# Sheet1.net
KiCad netlist of a schematic drawn in Altium Designer
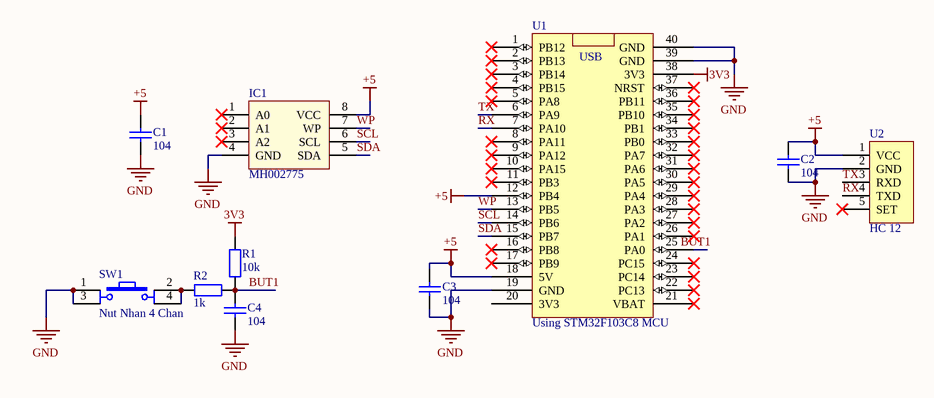
[diagram p0: Sheet1.SchDoc]

(export (version "E")
  (design (tool "Eeschema 10.0.6"))
  (components
    (comp (ref "C1")
      (value "104")
      (footprint "tu 0805")
      (description "Dán")
      (libsource (lib "THU VIEN SCH") (part "Tu 0805 104 50V 10%"))
    )
    (comp (ref "C2")
      (value "104")
      (footprint "tu 0805")
      (description "Dán")
      (libsource (lib "THU VIEN SCH") (part "Tu 0805 104 50V 10%"))
    )
    (comp (ref "C3")
      (value "104")
      (footprint "tu 0805")
      (description "Dán")
      (libsource (lib "THU VIEN SCH") (part "Tu 0805 104 50V 10%"))
    )
    (comp (ref "C4")
      (value "104")
      (footprint "tu 0805")
      (description "Dán")
      (libsource (lib "THU VIEN SCH") (part "Tu 0805 104 50V 10%"))
    )
    (comp (ref "IC1")
      (value "MH002775")
      (footprint "DIP8")
      (description "Dán")
      (libsource (lib "THU VIEN SCH") (part "24Cxx_MH"))
    )
    (comp (ref "R1")
      (value "10k")
      (footprint "tro smd 0805")
      (description "Dán")
      (libsource (lib "THU VIEN SCH") (part "Tro 0805 1% 10k"))
    )
    (comp (ref "R2")
      (value "1k")
      (footprint "tro smd 0805")
      (description "Dán")
      (libsource (lib "THU VIEN SCH") (part "Tro 0805 1% 3.3k"))
    )
    (comp (ref "SW1")
      (value "Nut Nhan 4 Chan")
      (footprint "SW4")
      (description "Cắm")
      (libsource (lib "THU VIEN SCH") (part "Nut Nhan 4 Chan"))
    )
    (comp (ref "U1")
      (value "Using STM32F103C8 MCU")
      (footprint "STM32 BluePill")
      (libsource (lib "My_Lib") (part "BluePill"))
    )
    (comp (ref "U2") (value "HC 12") (footprint "HC 12") (libsource (lib "My_Lib") (part "HC 12")))
  )
  (nets
    (net (code "1") (name "+5") (class "Default")
      (node (ref "C1") (pin "1") (pinfunction "1_1") (pintype "passive"))
      (node (ref "C2") (pin "1") (pinfunction "1_1") (pintype "passive"))
      (node (ref "C3") (pin "1") (pinfunction "1_1") (pintype "passive"))
      (node (ref "IC1") (pin "8") (pinfunction "VCC_8") (pintype "power_in"))
      (node (ref "U1") (pin "12") (pinfunction "PB4_12") (pintype "bidirectional"))
      (node (ref "U1") (pin "18") (pinfunction "5V_18") (pintype "power_in"))
      (node (ref "U2") (pin "1") (pinfunction "VCC_1") (pintype "passive"))
    )
    (net (code "2") (name "/BUT1") (class "Default")
      (node (ref "C4") (pin "1") (pinfunction "1_1") (pintype "passive"))
      (node (ref "R1") (pin "1") (pinfunction "1_1") (pintype "passive"))
      (node (ref "R2") (pin "2") (pinfunction "2_2") (pintype "passive"))
    )
    (net (code "3") (name "/RX") (class "Default")
      (node (ref "U1") (pin "7") (pinfunction "PA10_7") (pintype "bidirectional"))
      (node (ref "U2") (pin "4") (pinfunction "TXD_4") (pintype "passive"))
    )
    (net (code "4") (name "/SCL") (class "Default")
      (node (ref "IC1") (pin "6") (pinfunction "SCL_6") (pintype "passive"))
      (node (ref "U1") (pin "14") (pinfunction "PB6_14") (pintype "bidirectional"))
    )
    (net (code "5") (name "/SDA") (class "Default")
      (node (ref "IC1") (pin "5") (pinfunction "SDA_5") (pintype "passive"))
      (node (ref "U1") (pin "15") (pinfunction "PB7_15") (pintype "bidirectional"))
    )
    (net (code "6") (name "/TX") (class "Default")
      (node (ref "U1") (pin "6") (pinfunction "PA9_6") (pintype "bidirectional"))
      (node (ref "U2") (pin "3") (pinfunction "RXD_3") (pintype "passive"))
    )
    (net (code "7") (name "/WP") (class "Default")
      (node (ref "IC1") (pin "7") (pinfunction "WP_7") (pintype "passive"))
      (node (ref "U1") (pin "13") (pinfunction "PB5_13") (pintype "bidirectional"))
    )
    (net (code "8") (name "3V3") (class "Default")
      (node (ref "R1") (pin "2") (pinfunction "2_2") (pintype "passive"))
      (node (ref "U1") (pin "38") (pinfunction "3V3_38") (pintype "power_in"))
    )
    (net (code "9") (name "GND") (class "Default")
      (node (ref "C1") (pin "2") (pinfunction "2_2") (pintype "passive"))
      (node (ref "C2") (pin "2") (pinfunction "2_2") (pintype "passive"))
      (node (ref "C3") (pin "2") (pinfunction "2_2") (pintype "passive"))
      (node (ref "C4") (pin "2") (pinfunction "2_2") (pintype "passive"))
      (node (ref "IC1") (pin "4") (pinfunction "GND_4") (pintype "power_in"))
      (node (ref "SW1") (pin "1") (pintype "passive"))
      (node (ref "SW1") (pin "3") (pintype "passive"))
      (node (ref "U1") (pin "19") (pinfunction "GND_19") (pintype "power_in"))
      (node (ref "U1") (pin "39") (pinfunction "GND_39") (pintype "power_in"))
      (node (ref "U1") (pin "40") (pinfunction "GND_40") (pintype "power_in"))
      (node (ref "U2") (pin "2") (pinfunction "GND_2") (pintype "passive"))
    )
    (net (code "10") (name "Net-(R2-Pad1)") (class "Default")
      (node (ref "R2") (pin "1") (pinfunction "1_1") (pintype "passive"))
      (node (ref "SW1") (pin "2") (pintype "passive"))
      (node (ref "SW1") (pin "4") (pintype "passive"))
    )
    (net (code "11") (name "unconnected-(IC1-A0-Pad1)") (class "Default")
      (node (ref "IC1") (pin "1") (pinfunction "A0_1") (pintype "passive+no_connect"))
    )
    (net (code "12") (name "unconnected-(IC1-A1-Pad2)") (class "Default")
      (node (ref "IC1") (pin "2") (pinfunction "A1_2") (pintype "passive+no_connect"))
    )
    (net (code "13") (name "unconnected-(IC1-A2-Pad3)") (class "Default")
      (node (ref "IC1") (pin "3") (pinfunction "A2_3") (pintype "passive+no_connect"))
    )
    (net (code "14") (name "unconnected-(U1-3V3-Pad20)") (class "Default")
      (node (ref "U1") (pin "20") (pinfunction "3V3_20") (pintype "power_in"))
    )
    (net (code "15") (name "unconnected-(U1-NRST-Pad37)") (class "Default")
      (node (ref "U1") (pin "37") (pinfunction "NRST_37") (pintype "bidirectional+no_connect"))
    )
    (net (code "16") (name "unconnected-(U1-PA0-Pad25)") (class "Default")
      (node (ref "U1") (pin "25") (pinfunction "PA0_25") (pintype "bidirectional"))
    )
    (net (code "17") (name "unconnected-(U1-PA1-Pad26)") (class "Default")
      (node (ref "U1") (pin "26") (pinfunction "PA1_26") (pintype "bidirectional+no_connect"))
    )
    (net (code "18") (name "unconnected-(U1-PA2-Pad27)") (class "Default")
      (node (ref "U1") (pin "27") (pinfunction "PA2_27") (pintype "bidirectional+no_connect"))
    )
    (net (code "19") (name "unconnected-(U1-PA3-Pad28)") (class "Default")
      (node (ref "U1") (pin "28") (pinfunction "PA3_28") (pintype "bidirectional+no_connect"))
    )
    (net (code "20") (name "unconnected-(U1-PA4-Pad29)") (class "Default")
      (node (ref "U1") (pin "29") (pinfunction "PA4_29") (pintype "bidirectional+no_connect"))
    )
    (net (code "21") (name "unconnected-(U1-PA5-Pad30)") (class "Default")
      (node (ref "U1") (pin "30") (pinfunction "PA5_30") (pintype "bidirectional+no_connect"))
    )
    (net (code "22") (name "unconnected-(U1-PA6-Pad31)") (class "Default")
      (node (ref "U1") (pin "31") (pinfunction "PA6_31") (pintype "bidirectional+no_connect"))
    )
    (net (code "23") (name "unconnected-(U1-PA7-Pad32)") (class "Default")
      (node (ref "U1") (pin "32") (pinfunction "PA7_32") (pintype "bidirectional+no_connect"))
    )
    (net (code "24") (name "unconnected-(U1-PA8-Pad5)") (class "Default")
      (node (ref "U1") (pin "5") (pinfunction "PA8_5") (pintype "bidirectional+no_connect"))
    )
    (net (code "25") (name "unconnected-(U1-PA11-Pad8)") (class "Default")
      (node (ref "U1") (pin "8") (pinfunction "PA11_8") (pintype "bidirectional+no_connect"))
    )
    (net (code "26") (name "unconnected-(U1-PA12-Pad9)") (class "Default")
      (node (ref "U1") (pin "9") (pinfunction "PA12_9") (pintype "bidirectional+no_connect"))
    )
    (net (code "27") (name "unconnected-(U1-PA15-Pad10)") (class "Default")
      (node (ref "U1") (pin "10") (pinfunction "PA15_10") (pintype "bidirectional+no_connect"))
    )
    (net (code "28") (name "unconnected-(U1-PB0-Pad33)") (class "Default")
      (node (ref "U1") (pin "33") (pinfunction "PB0_33") (pintype "bidirectional+no_connect"))
    )
    (net (code "29") (name "unconnected-(U1-PB1-Pad34)") (class "Default")
      (node (ref "U1") (pin "34") (pinfunction "PB1_34") (pintype "bidirectional+no_connect"))
    )
    (net (code "30") (name "unconnected-(U1-PB3-Pad11)") (class "Default")
      (node (ref "U1") (pin "11") (pinfunction "PB3_11") (pintype "bidirectional+no_connect"))
    )
    (net (code "31") (name "unconnected-(U1-PB8-Pad16)") (class "Default")
      (node (ref "U1") (pin "16") (pinfunction "PB8_16") (pintype "bidirectional+no_connect"))
    )
    (net (code "32") (name "unconnected-(U1-PB9-Pad17)") (class "Default")
      (node (ref "U1") (pin "17") (pinfunction "PB9_17") (pintype "bidirectional+no_connect"))
    )
    (net (code "33") (name "unconnected-(U1-PB10-Pad35)") (class "Default")
      (node (ref "U1") (pin "35") (pinfunction "PB10_35") (pintype "bidirectional+no_connect"))
    )
    (net (code "34") (name "unconnected-(U1-PB11-Pad36)") (class "Default")
      (node (ref "U1") (pin "36") (pinfunction "PB11_36") (pintype "bidirectional+no_connect"))
    )
    (net (code "35") (name "unconnected-(U1-PB12-Pad1)") (class "Default")
      (node (ref "U1") (pin "1") (pinfunction "PB12_1") (pintype "bidirectional+no_connect"))
    )
    (net (code "36") (name "unconnected-(U1-PB13-Pad2)") (class "Default")
      (node (ref "U1") (pin "2") (pinfunction "PB13_2") (pintype "bidirectional+no_connect"))
    )
    (net (code "37") (name "unconnected-(U1-PB14-Pad3)") (class "Default")
      (node (ref "U1") (pin "3") (pinfunction "PB14_3") (pintype "bidirectional+no_connect"))
    )
    (net (code "38") (name "unconnected-(U1-PB15-Pad4)") (class "Default")
      (node (ref "U1") (pin "4") (pinfunction "PB15_4") (pintype "bidirectional+no_connect"))
    )
    (net (code "39") (name "unconnected-(U1-PC13-Pad22)") (class "Default")
      (node (ref "U1") (pin "22") (pinfunction "PC13_22") (pintype "bidirectional+no_connect"))
    )
    (net (code "40") (name "unconnected-(U1-PC14-Pad23)") (class "Default")
      (node (ref "U1") (pin "23") (pinfunction "PC14_23") (pintype "bidirectional+no_connect"))
    )
    (net (code "41") (name "unconnected-(U1-PC15-Pad24)") (class "Default")
      (node (ref "U1") (pin "24") (pinfunction "PC15_24") (pintype "bidirectional+no_connect"))
    )
    (net (code "42") (name "unconnected-(U1-VBAT-Pad21)") (class "Default")
      (node (ref "U1") (pin "21") (pinfunction "VBAT_21") (pintype "power_in+no_connect"))
    )
    (net (code "43") (name "unconnected-(U2-SET-Pad5)") (class "Default")
      (node (ref "U2") (pin "5") (pinfunction "SET_5") (pintype "passive+no_connect"))
    )
  )
)
